# Mainboard.net
KiCad netlist of a schematic drawn in Altium Designer
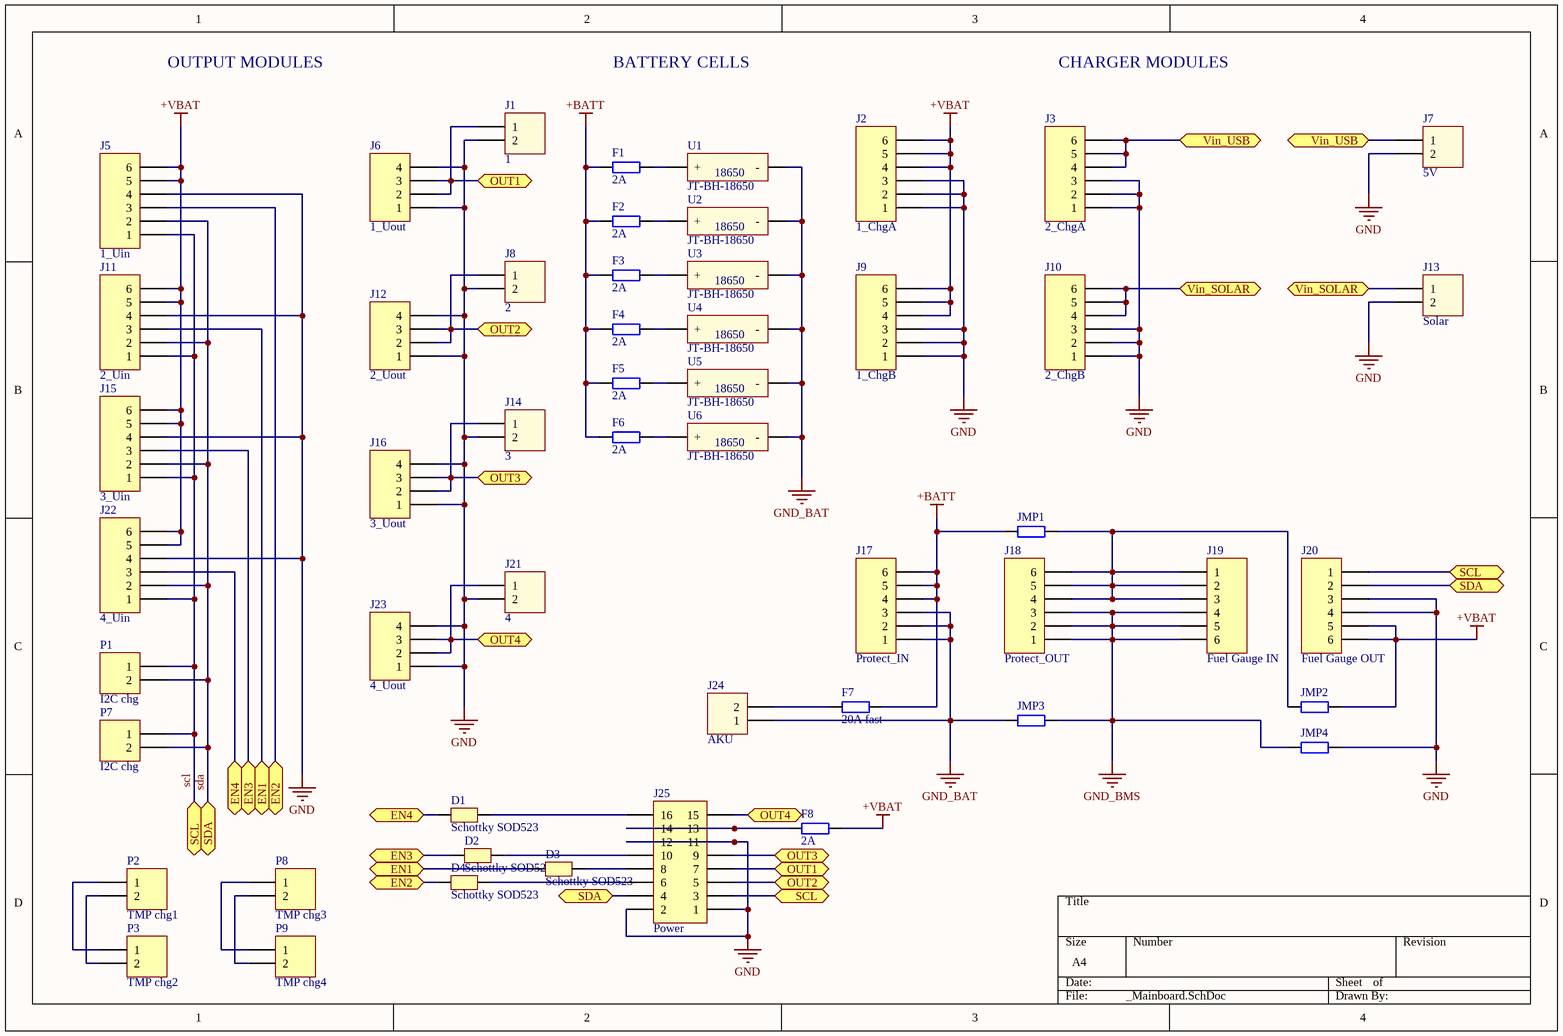
[diagram p0: _Mainboard.SchDoc]

(export (version "E")
  (design (tool "Eeschema 10.0.6"))
  (components
    (comp (ref "D1")
      (value "Schottky SOD523")
      (footprint "SOD523")
      (libsource (lib "GeneralComponents") (part "Resistor"))
    )
    (comp (ref "D2")
      (value "Schottky SOD523")
      (footprint "SOD523")
      (libsource (lib "GeneralComponents") (part "Resistor"))
    )
    (comp (ref "D3")
      (value "Schottky SOD523")
      (footprint "SOD523")
      (libsource (lib "GeneralComponents") (part "Resistor"))
    )
    (comp (ref "D4")
      (value "Schottky SOD523")
      (footprint "SOD523")
      (libsource (lib "GeneralComponents") (part "Resistor"))
    )
    (comp (ref "F1")
      (value "SMD fuse")
      (footprint "1206 RES")
      (fields (field (name "VALVE") "2A"))
      (libsource (lib "IKSOR_LIB_main") (part "Resistor"))
    )
    (comp (ref "F2")
      (value "SMD fuse")
      (footprint "1206 RES")
      (fields (field (name "VALVE") "2A"))
      (libsource (lib "IKSOR_LIB_main") (part "Resistor"))
    )
    (comp (ref "F3")
      (value "SMD fuse")
      (footprint "1206 RES")
      (fields (field (name "VALVE") "2A"))
      (libsource (lib "IKSOR_LIB_main") (part "Resistor"))
    )
    (comp (ref "F4")
      (value "SMD fuse")
      (footprint "1206 RES")
      (fields (field (name "VALVE") "2A"))
      (libsource (lib "IKSOR_LIB_main") (part "Resistor"))
    )
    (comp (ref "F5")
      (value "SMD fuse")
      (footprint "1206 RES")
      (fields (field (name "VALVE") "2A"))
      (libsource (lib "IKSOR_LIB_main") (part "Resistor"))
    )
    (comp (ref "F6")
      (value "SMD fuse")
      (footprint "1206 RES")
      (fields (field (name "VALVE") "2A"))
      (libsource (lib "IKSOR_LIB_main") (part "Resistor"))
    )
    (comp (ref "F7")
      (value "SMD fuse")
      (footprint "1206 RES")
      (description "Farnell  1832127")
      (fields (field (name "VALVE") "20A fast"))
      (libsource (lib "IKSOR_LIB_main") (part "Resistor"))
    )
    (comp (ref "F8")
      (value "SMD Fuse")
      (footprint "1206 RES")
      (description "SMD fuse")
      (fields (field (name "VALVE") "2A"))
      (libsource (lib "IKSOR_LIB_main") (part "Resistor"))
    )
    (comp (ref "J1")
      (value "1")
      (footprint "691213510002")
      (description "2P 5.08 screw terminal")
      (fields (field (name "PART NUMBER") "691213510002") (field (name "PUBLISHER") "Wurth Elektronik"))
      (libsource (lib "ALTIUM-TBL_5_08_2165S_HORIZONTAL_ENTRY_W_RISING_CAGE_69121351000xS-rev17b (1)") (part "691213510002"))
    )
    (comp (ref "J2")
      (value "1_ChgA")
      (footprint "HDR1X6")
      (description "Header, 6-Pin")
      (libsource (lib "Miscellaneous Connectors") (part "Header 6"))
    )
    (comp (ref "J3")
      (value "2_ChgA")
      (footprint "HDR1X6")
      (description "Header, 6-Pin")
      (libsource (lib "Miscellaneous Connectors") (part "Header 6"))
    )
    (comp (ref "J5")
      (value "1_Uin")
      (footprint "HDR1X6")
      (description "Header, 6-Pin")
      (libsource (lib "Miscellaneous Connectors") (part "Header 6"))
    )
    (comp (ref "J6")
      (value "1_Uout")
      (footprint "HDR1X4")
      (description "Header, 4-Pin")
      (fields (field (name "PUBLISHER") "Altium Limited"))
      (libsource (lib "Miscellaneous Connectors") (part "Header 4"))
    )
    (comp (ref "J7")
      (value "5V")
      (footprint "691213510002")
      (description "2P 5.08 screw terminal")
      (fields (field (name "PART NUMBER") "691213510002") (field (name "PUBLISHER") "Wurth Elektronik"))
      (libsource (lib "ALTIUM-TBL_5_08_2165S_HORIZONTAL_ENTRY_W_RISING_CAGE_69121351000xS-rev17b (1)") (part "691213510002"))
    )
    (comp (ref "J8")
      (value "2")
      (footprint "691213510002")
      (description "2P 5.08 screw terminal")
      (fields (field (name "PART NUMBER") "691213510002") (field (name "PUBLISHER") "Wurth Elektronik"))
      (libsource (lib "ALTIUM-TBL_5_08_2165S_HORIZONTAL_ENTRY_W_RISING_CAGE_69121351000xS-rev17b (1)") (part "691213510002"))
    )
    (comp (ref "J9")
      (value "1_ChgB")
      (footprint "HDR1X6")
      (description "Header, 6-Pin")
      (libsource (lib "Miscellaneous Connectors") (part "Header 6"))
    )
    (comp (ref "J10")
      (value "2_ChgB")
      (footprint "HDR1X6")
      (description "Header, 6-Pin")
      (libsource (lib "Miscellaneous Connectors") (part "Header 6"))
    )
    (comp (ref "J11")
      (value "2_Uin")
      (footprint "HDR1X6")
      (description "Header, 6-Pin")
      (libsource (lib "Miscellaneous Connectors") (part "Header 6"))
    )
    (comp (ref "J12")
      (value "2_Uout")
      (footprint "HDR1X4")
      (description "Header, 4-Pin")
      (fields (field (name "PUBLISHER") "Altium Limited"))
      (libsource (lib "Miscellaneous Connectors") (part "Header 4"))
    )
    (comp (ref "J13")
      (value "Solar")
      (footprint "691213510002")
      (description "2P 5.08 screw terminal")
      (fields (field (name "PART NUMBER") "691213510002") (field (name "PUBLISHER") "Wurth Elektronik"))
      (libsource (lib "ALTIUM-TBL_5_08_2165S_HORIZONTAL_ENTRY_W_RISING_CAGE_69121351000xS-rev17b (1)") (part "691213510002"))
    )
    (comp (ref "J14")
      (value "3")
      (footprint "691213510002")
      (description "2P 5.08 screw terminal")
      (fields (field (name "PART NUMBER") "691213510002") (field (name "PUBLISHER") "Wurth Elektronik"))
      (libsource (lib "ALTIUM-TBL_5_08_2165S_HORIZONTAL_ENTRY_W_RISING_CAGE_69121351000xS-rev17b (1)") (part "691213510002"))
    )
    (comp (ref "J15")
      (value "3_Uin")
      (footprint "HDR1X6")
      (description "Header, 6-Pin")
      (libsource (lib "Miscellaneous Connectors") (part "Header 6"))
    )
    (comp (ref "J16")
      (value "3_Uout")
      (footprint "HDR1X4")
      (description "Header, 4-Pin")
      (fields (field (name "PUBLISHER") "Altium Limited"))
      (libsource (lib "Miscellaneous Connectors") (part "Header 4"))
    )
    (comp (ref "J17")
      (value "Protect_IN")
      (footprint "HDR1X6")
      (description "Header, 6-Pin")
      (libsource (lib "Miscellaneous Connectors") (part "Header 6"))
    )
    (comp (ref "J18")
      (value "Protect_OUT")
      (footprint "HDR1X6")
      (description "Header, 6-Pin")
      (libsource (lib "Miscellaneous Connectors") (part "Header 6"))
    )
    (comp (ref "J19")
      (value "Fuel Gauge IN")
      (footprint "HDR1X6")
      (description "Header, 6-Pin")
      (libsource (lib "") (part "Header 6_2"))
    )
    (comp (ref "J20")
      (value "Fuel Gauge OUT")
      (footprint "HDR1X6")
      (description "Header, 6-Pin")
      (libsource (lib "") (part "Header 6_1"))
    )
    (comp (ref "J21")
      (value "4")
      (footprint "691213510002")
      (description "2P 5.08 screw terminal")
      (fields (field (name "PART NUMBER") "691213510002") (field (name "PUBLISHER") "Wurth Elektronik"))
      (libsource (lib "ALTIUM-TBL_5_08_2165S_HORIZONTAL_ENTRY_W_RISING_CAGE_69121351000xS-rev17b (1)") (part "691213510002"))
    )
    (comp (ref "J22")
      (value "4_Uin")
      (footprint "HDR1X6")
      (description "Header, 6-Pin")
      (libsource (lib "Miscellaneous Connectors") (part "Header 6"))
    )
    (comp (ref "J23")
      (value "4_Uout")
      (footprint "HDR1X4")
      (description "Header, 4-Pin")
      (fields (field (name "PUBLISHER") "Altium Limited"))
      (libsource (lib "Miscellaneous Connectors") (part "Header 4"))
    )
    (comp (ref "J24")
      (value "AKU")
      (footprint "691213510002")
      (description "2P 5.08 screw terminal")
      (fields (field (name "PART NUMBER") "691213510002") (field (name "PUBLISHER") "Wurth Elektronik"))
      (libsource (lib "") (part "691213510002_1"))
    )
    (comp (ref "J25")
      (value "Power")
      (footprint "61201621621")
      (description "WR-BHD 2.54mm Male Box Header")
      (fields
        (field (name "MANUFACTURER") "Wurth Elektronik")
        (field (name "PARTNO") "61201621621")
        (field (name "CREATED BY") "Baojun Chen")
      )
      (libsource (lib "ALTIUM-BHD_2_54_MALE_BOX_HEADER_6120XX21621-rev16b") (part "61201621621"))
    )
    (comp (ref "JMP1")
      (value "Resistor generic")
      (footprint "0603 RES")
      (description "Resistor SMD")
      (libsource (lib "IKSOR_LIB_main") (part "Resistor"))
    )
    (comp (ref "JMP2")
      (value "Resistor generic")
      (footprint "0603 RES")
      (description "Resistor SMD")
      (libsource (lib "IKSOR_LIB_main") (part "Resistor"))
    )
    (comp (ref "JMP3")
      (value "Resistor generic")
      (footprint "0603 RES")
      (description "Resistor SMD")
      (libsource (lib "IKSOR_LIB_main") (part "Resistor"))
    )
    (comp (ref "JMP4")
      (value "Resistor generic")
      (footprint "0603 RES")
      (description "Resistor SMD")
      (libsource (lib "IKSOR_LIB_main") (part "Resistor"))
    )
    (comp (ref "P1")
      (value "I2C chg")
      (footprint "HDR1X2")
      (description "Header, 2-Pin")
      (fields (field (name "PUBLISHER") "Altium Limited"))
      (libsource (lib "") (part "Header 2_1"))
    )
    (comp (ref "P2")
      (value "TMP chg1")
      (footprint "HDR1X2")
      (description "Header, 2-Pin")
      (fields (field (name "PUBLISHER") "Altium Limited"))
      (libsource (lib "Miscellaneous Connectors") (part "Header 2"))
    )
    (comp (ref "P3")
      (value "TMP chg2")
      (footprint "HDR1X2")
      (description "Header, 2-Pin")
      (fields (field (name "PUBLISHER") "Altium Limited"))
      (libsource (lib "Miscellaneous Connectors") (part "Header 2"))
    )
    (comp (ref "P7")
      (value "I2C chg")
      (footprint "HDR1X2")
      (description "Header, 2-Pin")
      (fields (field (name "PUBLISHER") "Altium Limited"))
      (libsource (lib "") (part "Header 2_1"))
    )
    (comp (ref "P8")
      (value "TMP chg3")
      (footprint "HDR1X2")
      (description "Header, 2-Pin")
      (fields (field (name "PUBLISHER") "Altium Limited"))
      (libsource (lib "Miscellaneous Connectors") (part "Header 2"))
    )
    (comp (ref "P9")
      (value "TMP chg4")
      (footprint "HDR1X2")
      (description "Header, 2-Pin")
      (fields (field (name "PUBLISHER") "Altium Limited"))
      (libsource (lib "Miscellaneous Connectors") (part "Header 2"))
    )
    (comp (ref "U1")
      (value "JT-BH-18650")
      (footprint "18650 holder")
      (libsource (lib "IKSOR_LIB_main") (part "18650 holder"))
    )
    (comp (ref "U2")
      (value "JT-BH-18650")
      (footprint "18650 holder")
      (libsource (lib "IKSOR_LIB_main") (part "18650 holder"))
    )
    (comp (ref "U3")
      (value "JT-BH-18650")
      (footprint "18650 holder")
      (libsource (lib "IKSOR_LIB_main") (part "18650 holder"))
    )
    (comp (ref "U4")
      (value "JT-BH-18650")
      (footprint "18650 holder")
      (libsource (lib "IKSOR_LIB_main") (part "18650 holder"))
    )
    (comp (ref "U5")
      (value "JT-BH-18650")
      (footprint "18650 holder")
      (libsource (lib "IKSOR_LIB_main") (part "18650 holder"))
    )
    (comp (ref "U6")
      (value "JT-BH-18650")
      (footprint "18650 holder")
      (libsource (lib "IKSOR_LIB_main") (part "18650 holder"))
    )
  )
  (nets
    (net (code "1") (name "+BATT") (class "Default")
      (node (ref "F1") (pin "1") (pinfunction "1_1") (pintype "passive"))
      (node (ref "F2") (pin "1") (pinfunction "1_1") (pintype "passive"))
      (node (ref "F3") (pin "1") (pinfunction "1_1") (pintype "passive"))
      (node (ref "F4") (pin "1") (pinfunction "1_1") (pintype "passive"))
      (node (ref "F5") (pin "1") (pinfunction "1_1") (pintype "passive"))
      (node (ref "F6") (pin "1") (pinfunction "1_1") (pintype "passive"))
      (node (ref "F7") (pin "2") (pinfunction "2_2") (pintype "passive"))
      (node (ref "J17") (pin "4") (pinfunction "4_4") (pintype "passive"))
      (node (ref "J17") (pin "5") (pinfunction "5_5") (pintype "passive"))
      (node (ref "J17") (pin "6") (pinfunction "6_6") (pintype "passive"))
      (node (ref "JMP1") (pin "1") (pinfunction "1_1") (pintype "passive"))
    )
    (net (code "2") (name "+VBAT") (class "Default")
      (node (ref "F8") (pin "2") (pinfunction "2_2") (pintype "passive"))
      (node (ref "J11") (pin "5") (pinfunction "5_5") (pintype "passive"))
      (node (ref "J11") (pin "6") (pinfunction "6_6") (pintype "passive"))
      (node (ref "J15") (pin "5") (pinfunction "5_5") (pintype "passive"))
      (node (ref "J15") (pin "6") (pinfunction "6_6") (pintype "passive"))
      (node (ref "J2") (pin "4") (pinfunction "4_4") (pintype "passive"))
      (node (ref "J2") (pin "5") (pinfunction "5_5") (pintype "passive"))
      (node (ref "J2") (pin "6") (pinfunction "6_6") (pintype "passive"))
      (node (ref "J20") (pin "5") (pinfunction "5_5") (pintype "passive"))
      (node (ref "J20") (pin "6") (pinfunction "6_6") (pintype "passive"))
      (node (ref "J22") (pin "5") (pinfunction "5_5") (pintype "passive"))
      (node (ref "J22") (pin "6") (pinfunction "6_6") (pintype "passive"))
      (node (ref "J5") (pin "5") (pinfunction "5_5") (pintype "passive"))
      (node (ref "J5") (pin "6") (pinfunction "6_6") (pintype "passive"))
      (node (ref "J9") (pin "4") (pinfunction "4_4") (pintype "passive"))
      (node (ref "J9") (pin "5") (pinfunction "5_5") (pintype "passive"))
      (node (ref "J9") (pin "6") (pinfunction "6_6") (pintype "passive"))
      (node (ref "JMP2") (pin "2") (pinfunction "2_2") (pintype "passive"))
    )
    (net (code "3") (name "/EN1") (class "Default")
      (node (ref "D3") (pin "2") (pinfunction "2_2") (pintype "passive"))
      (node (ref "J11") (pin "3") (pinfunction "3_3") (pintype "passive"))
    )
    (net (code "4") (name "/EN2") (class "Default")
      (node (ref "D4") (pin "2") (pinfunction "2_2") (pintype "passive"))
      (node (ref "J5") (pin "3") (pinfunction "3_3") (pintype "passive"))
    )
    (net (code "5") (name "/EN3") (class "Default")
      (node (ref "D2") (pin "2") (pinfunction "2_2") (pintype "passive"))
      (node (ref "J15") (pin "3") (pinfunction "3_3") (pintype "passive"))
    )
    (net (code "6") (name "/EN4") (class "Default")
      (node (ref "D1") (pin "2") (pinfunction "2_2") (pintype "passive"))
      (node (ref "J22") (pin "3") (pinfunction "3_3") (pintype "passive"))
    )
    (net (code "7") (name "/OUT1") (class "Default")
      (node (ref "J1") (pin "1") (pinfunction "1_1") (pintype "passive"))
      (node (ref "J25") (pin "7") (pinfunction "7_7") (pintype "passive"))
      (node (ref "J6") (pin "2") (pinfunction "2_2") (pintype "passive"))
      (node (ref "J6") (pin "3") (pinfunction "3_3") (pintype "passive"))
    )
    (net (code "8") (name "/OUT2") (class "Default")
      (node (ref "J12") (pin "2") (pinfunction "2_2") (pintype "passive"))
      (node (ref "J12") (pin "3") (pinfunction "3_3") (pintype "passive"))
      (node (ref "J25") (pin "5") (pinfunction "5_5") (pintype "passive"))
      (node (ref "J8") (pin "1") (pinfunction "1_1") (pintype "passive"))
    )
    (net (code "9") (name "/OUT3") (class "Default")
      (node (ref "J14") (pin "1") (pinfunction "1_1") (pintype "passive"))
      (node (ref "J16") (pin "2") (pinfunction "2_2") (pintype "passive"))
      (node (ref "J16") (pin "3") (pinfunction "3_3") (pintype "passive"))
      (node (ref "J25") (pin "9") (pinfunction "9_9") (pintype "passive"))
    )
    (net (code "10") (name "/OUT4") (class "Default")
      (node (ref "J21") (pin "1") (pinfunction "1_1") (pintype "passive"))
      (node (ref "J23") (pin "2") (pinfunction "2_2") (pintype "passive"))
      (node (ref "J23") (pin "3") (pinfunction "3_3") (pintype "passive"))
      (node (ref "J25") (pin "15") (pinfunction "15_15") (pintype "passive"))
    )
    (net (code "11") (name "/Vin_SOLAR") (class "Default")
      (node (ref "J10") (pin "4") (pinfunction "4_4") (pintype "passive"))
      (node (ref "J10") (pin "5") (pinfunction "5_5") (pintype "passive"))
      (node (ref "J10") (pin "6") (pinfunction "6_6") (pintype "passive"))
      (node (ref "J13") (pin "1") (pinfunction "1_1") (pintype "passive"))
    )
    (net (code "12") (name "/Vin_USB") (class "Default")
      (node (ref "J3") (pin "4") (pinfunction "4_4") (pintype "passive"))
      (node (ref "J3") (pin "5") (pinfunction "5_5") (pintype "passive"))
      (node (ref "J3") (pin "6") (pinfunction "6_6") (pintype "passive"))
      (node (ref "J7") (pin "1") (pinfunction "1_1") (pintype "passive"))
    )
    (net (code "13") (name "/scl") (class "Default")
      (node (ref "J11") (pin "1") (pinfunction "1_1") (pintype "passive"))
      (node (ref "J15") (pin "1") (pinfunction "1_1") (pintype "passive"))
      (node (ref "J20") (pin "1") (pinfunction "1_1") (pintype "passive"))
      (node (ref "J22") (pin "1") (pinfunction "1_1") (pintype "passive"))
      (node (ref "J25") (pin "3") (pinfunction "3_3") (pintype "passive"))
      (node (ref "J5") (pin "1") (pinfunction "1_1") (pintype "passive"))
      (node (ref "P1") (pin "1") (pinfunction "1_1") (pintype "passive"))
      (node (ref "P7") (pin "1") (pinfunction "1_1") (pintype "passive"))
    )
    (net (code "14") (name "/sda") (class "Default")
      (node (ref "J11") (pin "2") (pinfunction "2_2") (pintype "passive"))
      (node (ref "J15") (pin "2") (pinfunction "2_2") (pintype "passive"))
      (node (ref "J20") (pin "2") (pinfunction "2_2") (pintype "passive"))
      (node (ref "J22") (pin "2") (pinfunction "2_2") (pintype "passive"))
      (node (ref "J25") (pin "4") (pinfunction "4_4") (pintype "passive"))
      (node (ref "J5") (pin "2") (pinfunction "2_2") (pintype "passive"))
      (node (ref "P1") (pin "2") (pinfunction "2_2") (pintype "passive"))
      (node (ref "P7") (pin "2") (pinfunction "2_2") (pintype "passive"))
    )
    (net (code "15") (name "GND") (class "Default")
      (node (ref "J1") (pin "2") (pinfunction "2_2") (pintype "passive"))
      (node (ref "J10") (pin "1") (pinfunction "1_1") (pintype "passive"))
      (node (ref "J10") (pin "2") (pinfunction "2_2") (pintype "passive"))
      (node (ref "J10") (pin "3") (pinfunction "3_3") (pintype "passive"))
      (node (ref "J11") (pin "4") (pinfunction "4_4") (pintype "passive"))
      (node (ref "J12") (pin "1") (pinfunction "1_1") (pintype "passive"))
      (node (ref "J12") (pin "4") (pinfunction "4_4") (pintype "passive"))
      (node (ref "J13") (pin "2") (pinfunction "2_2") (pintype "passive"))
      (node (ref "J14") (pin "2") (pinfunction "2_2") (pintype "passive"))
      (node (ref "J15") (pin "4") (pinfunction "4_4") (pintype "passive"))
      (node (ref "J16") (pin "1") (pinfunction "1_1") (pintype "passive"))
      (node (ref "J16") (pin "4") (pinfunction "4_4") (pintype "passive"))
      (node (ref "J2") (pin "1") (pinfunction "1_1") (pintype "passive"))
      (node (ref "J2") (pin "2") (pinfunction "2_2") (pintype "passive"))
      (node (ref "J2") (pin "3") (pinfunction "3_3") (pintype "passive"))
      (node (ref "J20") (pin "3") (pinfunction "3_3") (pintype "passive"))
      (node (ref "J20") (pin "4") (pinfunction "4_4") (pintype "passive"))
      (node (ref "J21") (pin "2") (pinfunction "2_2") (pintype "passive"))
      (node (ref "J22") (pin "4") (pinfunction "4_4") (pintype "passive"))
      (node (ref "J23") (pin "1") (pinfunction "1_1") (pintype "passive"))
      (node (ref "J23") (pin "4") (pinfunction "4_4") (pintype "passive"))
      (node (ref "J25") (pin "1") (pinfunction "1_1") (pintype "passive"))
      (node (ref "J25") (pin "11") (pinfunction "11_11") (pintype "passive"))
      (node (ref "J25") (pin "12") (pinfunction "12_12") (pintype "passive"))
      (node (ref "J25") (pin "2") (pinfunction "2_2") (pintype "passive"))
      (node (ref "J3") (pin "1") (pinfunction "1_1") (pintype "passive"))
      (node (ref "J3") (pin "2") (pinfunction "2_2") (pintype "passive"))
      (node (ref "J3") (pin "3") (pinfunction "3_3") (pintype "passive"))
      (node (ref "J5") (pin "4") (pinfunction "4_4") (pintype "passive"))
      (node (ref "J6") (pin "1") (pinfunction "1_1") (pintype "passive"))
      (node (ref "J6") (pin "4") (pinfunction "4_4") (pintype "passive"))
      (node (ref "J7") (pin "2") (pinfunction "2_2") (pintype "passive"))
      (node (ref "J8") (pin "2") (pinfunction "2_2") (pintype "passive"))
      (node (ref "J9") (pin "1") (pinfunction "1_1") (pintype "passive"))
      (node (ref "J9") (pin "2") (pinfunction "2_2") (pintype "passive"))
      (node (ref "J9") (pin "3") (pinfunction "3_3") (pintype "passive"))
      (node (ref "JMP4") (pin "2") (pinfunction "2_2") (pintype "passive"))
    )
    (net (code "16") (name "GND_BAT") (class "Default")
      (node (ref "J17") (pin "1") (pinfunction "1_1") (pintype "passive"))
      (node (ref "J17") (pin "2") (pinfunction "2_2") (pintype "passive"))
      (node (ref "J17") (pin "3") (pinfunction "3_3") (pintype "passive"))
      (node (ref "J24") (pin "1") (pinfunction "1_1") (pintype "passive"))
      (node (ref "JMP3") (pin "1") (pinfunction "1_1") (pintype "passive"))
      (node (ref "U1") (pin "2") (pinfunction "-_2") (pintype "passive"))
      (node (ref "U2") (pin "2") (pinfunction "-_2") (pintype "passive"))
      (node (ref "U3") (pin "2") (pinfunction "-_2") (pintype "passive"))
      (node (ref "U4") (pin "2") (pinfunction "-_2") (pintype "passive"))
      (node (ref "U5") (pin "2") (pinfunction "-_2") (pintype "passive"))
      (node (ref "U6") (pin "2") (pinfunction "-_2") (pintype "passive"))
    )
    (net (code "17") (name "GND_BMS") (class "Default")
      (node (ref "J18") (pin "1") (pinfunction "1_1") (pintype "passive"))
      (node (ref "J18") (pin "2") (pinfunction "2_2") (pintype "passive"))
      (node (ref "J18") (pin "3") (pinfunction "3_3") (pintype "passive"))
      (node (ref "J19") (pin "4") (pinfunction "4_4") (pintype "passive"))
      (node (ref "J19") (pin "5") (pinfunction "5_5") (pintype "passive"))
      (node (ref "J19") (pin "6") (pinfunction "6_6") (pintype "passive"))
      (node (ref "JMP3") (pin "2") (pinfunction "2_2") (pintype "passive"))
      (node (ref "JMP4") (pin "1") (pinfunction "1_1") (pintype "passive"))
    )
    (net (code "18") (name "Net-(D1-Pad1)") (class "Default")
      (node (ref "D1") (pin "1") (pinfunction "1_1") (pintype "passive"))
      (node (ref "J25") (pin "16") (pinfunction "16_16") (pintype "passive"))
    )
    (net (code "19") (name "Net-(D2-Pad1)") (class "Default")
      (node (ref "D2") (pin "1") (pinfunction "1_1") (pintype "passive"))
      (node (ref "J25") (pin "10") (pinfunction "10_10") (pintype "passive"))
    )
    (net (code "20") (name "Net-(D3-Pad1)") (class "Default")
      (node (ref "D3") (pin "1") (pinfunction "1_1") (pintype "passive"))
      (node (ref "J25") (pin "8") (pinfunction "8_8") (pintype "passive"))
    )
    (net (code "21") (name "Net-(D4-Pad1)") (class "Default")
      (node (ref "D4") (pin "1") (pinfunction "1_1") (pintype "passive"))
      (node (ref "J25") (pin "6") (pinfunction "6_6") (pintype "passive"))
    )
    (net (code "22") (name "Net-(F7-Pad1)") (class "Default")
      (node (ref "F7") (pin "1") (pinfunction "1_1") (pintype "passive"))
      (node (ref "J24") (pin "2") (pinfunction "2_2") (pintype "passive"))
    )
    (net (code "23") (name "Net-(F8-Pad1)") (class "Default")
      (node (ref "F8") (pin "1") (pinfunction "1_1") (pintype "passive"))
      (node (ref "J25") (pin "13") (pinfunction "13_13") (pintype "passive"))
      (node (ref "J25") (pin "14") (pinfunction "14_14") (pintype "passive"))
    )
    (net (code "24") (name "Net-(J18-Pad4)") (class "Default")
      (node (ref "J18") (pin "4") (pinfunction "4_4") (pintype "passive"))
      (node (ref "J18") (pin "5") (pinfunction "5_5") (pintype "passive"))
      (node (ref "J18") (pin "6") (pinfunction "6_6") (pintype "passive"))
      (node (ref "J19") (pin "1") (pinfunction "1_1") (pintype "passive"))
      (node (ref "J19") (pin "2") (pinfunction "2_2") (pintype "passive"))
      (node (ref "J19") (pin "3") (pinfunction "3_3") (pintype "passive"))
      (node (ref "JMP1") (pin "2") (pinfunction "2_2") (pintype "passive"))
      (node (ref "JMP2") (pin "1") (pinfunction "1_1") (pintype "passive"))
    )
    (net (code "25") (name "Net-(P2-Pad1)") (class "Default")
      (node (ref "P2") (pin "1") (pinfunction "1_1") (pintype "passive"))
      (node (ref "P3") (pin "1") (pinfunction "1_1") (pintype "passive"))
    )
    (net (code "26") (name "Net-(P2-Pad2)") (class "Default")
      (node (ref "P2") (pin "2") (pinfunction "2_2") (pintype "passive"))
      (node (ref "P3") (pin "2") (pinfunction "2_2") (pintype "passive"))
    )
    (net (code "27") (name "Net-(P8-Pad1)") (class "Default")
      (node (ref "P8") (pin "1") (pinfunction "1_1") (pintype "passive"))
      (node (ref "P9") (pin "1") (pinfunction "1_1") (pintype "passive"))
    )
    (net (code "28") (name "Net-(P8-Pad2)") (class "Default")
      (node (ref "P8") (pin "2") (pinfunction "2_2") (pintype "passive"))
      (node (ref "P9") (pin "2") (pinfunction "2_2") (pintype "passive"))
    )
    (net (code "29") (name "Net-(U1-+)") (class "Default")
      (node (ref "F1") (pin "2") (pinfunction "2_2") (pintype "passive"))
      (node (ref "U1") (pin "1") (pinfunction "+_1") (pintype "passive"))
    )
    (net (code "30") (name "Net-(U2-+)") (class "Default")
      (node (ref "F2") (pin "2") (pinfunction "2_2") (pintype "passive"))
      (node (ref "U2") (pin "1") (pinfunction "+_1") (pintype "passive"))
    )
    (net (code "31") (name "Net-(U3-+)") (class "Default")
      (node (ref "F3") (pin "2") (pinfunction "2_2") (pintype "passive"))
      (node (ref "U3") (pin "1") (pinfunction "+_1") (pintype "passive"))
    )
    (net (code "32") (name "Net-(U4-+)") (class "Default")
      (node (ref "F4") (pin "2") (pinfunction "2_2") (pintype "passive"))
      (node (ref "U4") (pin "1") (pinfunction "+_1") (pintype "passive"))
    )
    (net (code "33") (name "Net-(U5-+)") (class "Default")
      (node (ref "F5") (pin "2") (pinfunction "2_2") (pintype "passive"))
      (node (ref "U5") (pin "1") (pinfunction "+_1") (pintype "passive"))
    )
    (net (code "34") (name "Net-(U6-+)") (class "Default")
      (node (ref "F6") (pin "2") (pinfunction "2_2") (pintype "passive"))
      (node (ref "U6") (pin "1") (pinfunction "+_1") (pintype "passive"))
    )
  )
)
